# FIT_FPGA_A-C.net
KiCad netlist of a schematic drawn in Altium Designer
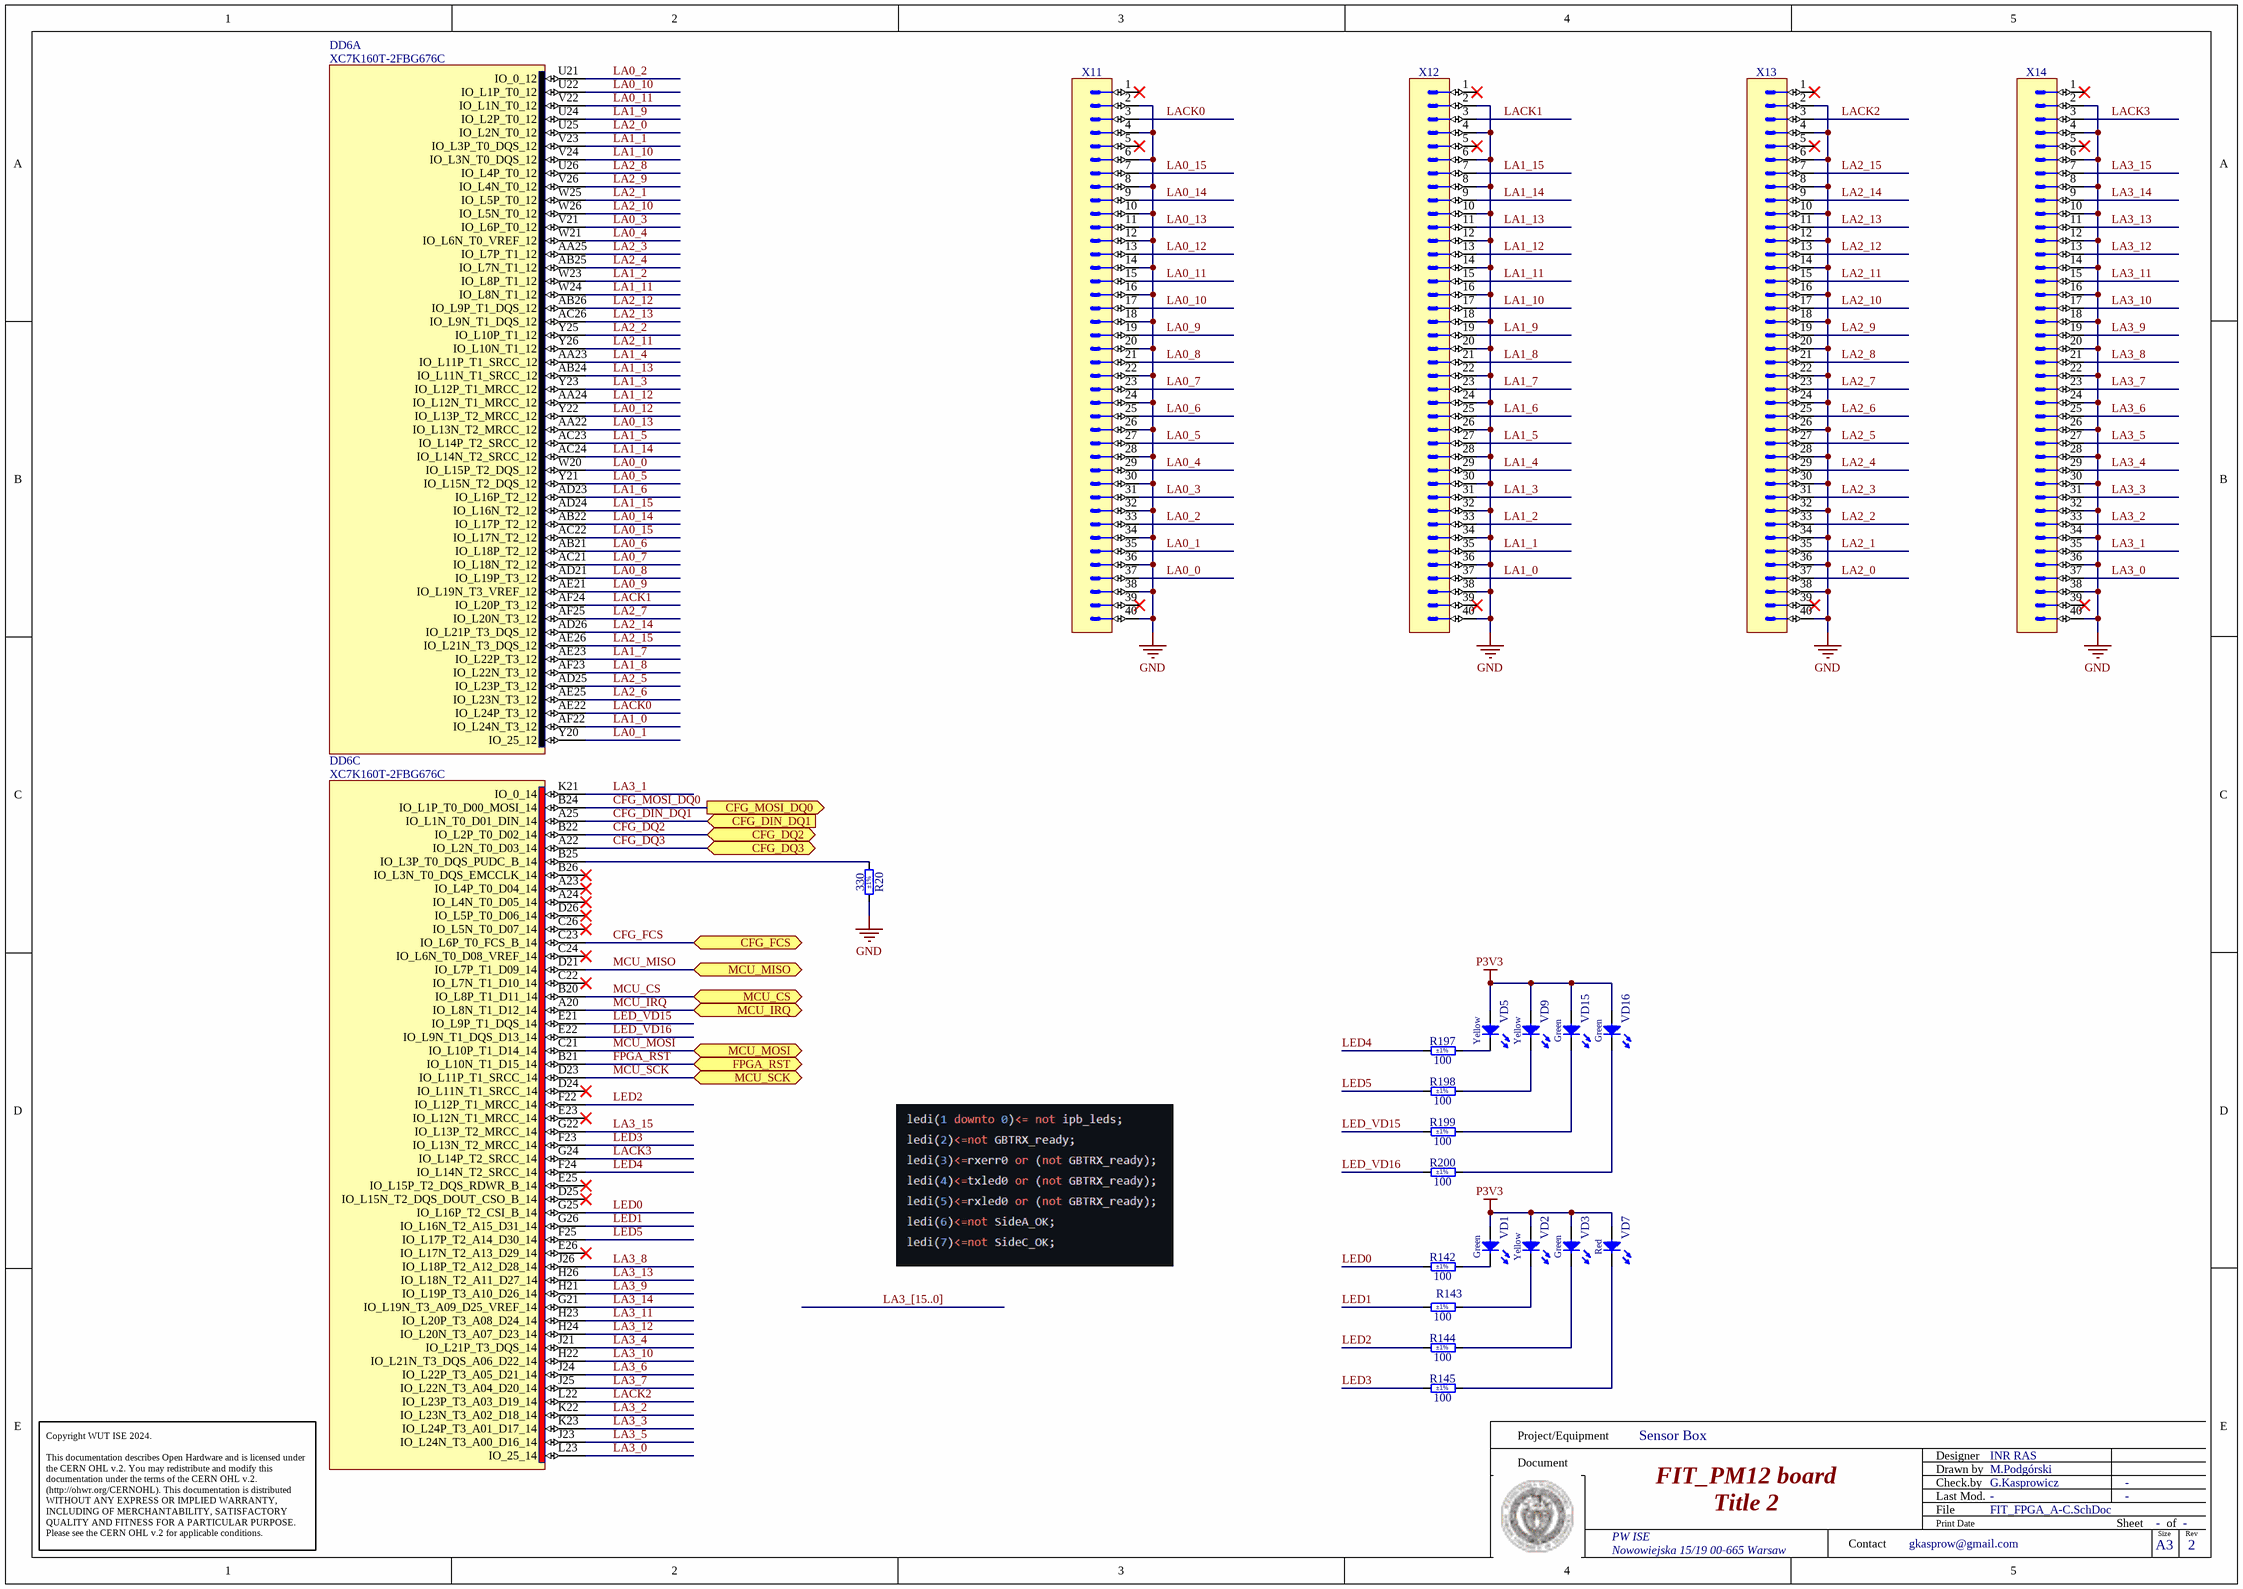
[diagram p0: FIT_FPGA_A-C.SchDoc]

(export (version "E")
  (design (tool "Eeschema 10.0.6"))
  (components
    (comp (ref "DD6")
      (value "XC7K160T-2FBG676C")
      (footprint "BGA676C100P26X26_2700X2700X254")
      (description "KINTEX-7, FPGA, 676-Ball BGA, Pb-Free")
      (fields (field (name "MANUFACTURER") "XILINX") (field (name "AUTHOR") "CERN DEM BC"))
      (libsource (lib "ICs And Semiconductors") (part "XC7K160T-xFBG676"))
    )
    (comp (ref "R20")
      (value "330")
      (footprint "RESC2012X60N")
      (description "Resistor - 1%")
      (fields
        (field (name "TOLERANCE") "±1%")
        (field (name "PART NUMBER") "R0805_330R_1%_0.125W_100PPM")
        (field (name "POWER") "0.125W")
        (field (name "AUTHOR") "CERN DEM JLC")
      )
      (libsource (lib "Resistors") (part "Resistor - 1%"))
    )
    (comp (ref "R142")
      (value "100")
      (footprint "RESC2012X60N")
      (description "Resistor - 1%")
      (fields
        (field (name "TOLERANCE") "±1%")
        (field (name "PART NUMBER") "R0805_100R_1%_0.125W_100PPM")
        (field (name "POWER") "0.125W")
        (field (name "AUTHOR") "CERN DEM JLC")
      )
      (libsource (lib "Resistors") (part "Resistor - 1%"))
    )
    (comp (ref "R143")
      (value "100")
      (footprint "RESC2012X60N")
      (description "Resistor - 1%")
      (fields
        (field (name "TOLERANCE") "±1%")
        (field (name "PART NUMBER") "R0805_100R_1%_0.125W_100PPM")
        (field (name "POWER") "0.125W")
        (field (name "AUTHOR") "CERN DEM JLC")
      )
      (libsource (lib "Resistors") (part "Resistor - 1%"))
    )
    (comp (ref "R144")
      (value "100")
      (footprint "RESC2012X60N")
      (description "Resistor - 1%")
      (fields
        (field (name "TOLERANCE") "±1%")
        (field (name "PART NUMBER") "R0805_100R_1%_0.125W_100PPM")
        (field (name "POWER") "0.125W")
        (field (name "AUTHOR") "CERN DEM JLC")
      )
      (libsource (lib "Resistors") (part "Resistor - 1%"))
    )
    (comp (ref "R145")
      (value "100")
      (footprint "RESC2012X60N")
      (description "Resistor - 1%")
      (fields
        (field (name "TOLERANCE") "±1%")
        (field (name "PART NUMBER") "R0805_100R_1%_0.125W_100PPM")
        (field (name "POWER") "0.125W")
        (field (name "AUTHOR") "CERN DEM JLC")
      )
      (libsource (lib "Resistors") (part "Resistor - 1%"))
    )
    (comp (ref "R197")
      (value "100")
      (footprint "RESC2012X60N")
      (description "Resistor - 1%")
      (fields
        (field (name "TOLERANCE") "±1%")
        (field (name "PART NUMBER") "R0805_100R_1%_0.125W_100PPM")
        (field (name "POWER") "0.125W")
        (field (name "AUTHOR") "CERN DEM JLC")
      )
      (libsource (lib "Resistors") (part "Resistor - 1%"))
    )
    (comp (ref "R198")
      (value "100")
      (footprint "RESC2012X60N")
      (description "Resistor - 1%")
      (fields
        (field (name "TOLERANCE") "±1%")
        (field (name "PART NUMBER") "R0805_100R_1%_0.125W_100PPM")
        (field (name "POWER") "0.125W")
        (field (name "AUTHOR") "CERN DEM JLC")
      )
      (libsource (lib "Resistors") (part "Resistor - 1%"))
    )
    (comp (ref "R199")
      (value "100")
      (footprint "RESC2012X60N")
      (description "Resistor - 1%")
      (fields
        (field (name "TOLERANCE") "±1%")
        (field (name "PART NUMBER") "R0805_100R_1%_0.125W_100PPM")
        (field (name "POWER") "0.125W")
        (field (name "AUTHOR") "CERN DEM JLC")
      )
      (libsource (lib "Resistors") (part "Resistor - 1%"))
    )
    (comp (ref "R200")
      (value "100")
      (footprint "RESC2012X60N")
      (description "Resistor - 1%")
      (fields
        (field (name "TOLERANCE") "±1%")
        (field (name "PART NUMBER") "R0805_100R_1%_0.125W_100PPM")
        (field (name "POWER") "0.125W")
        (field (name "AUTHOR") "CERN DEM JLC")
      )
      (libsource (lib "Resistors") (part "Resistor - 1%"))
    )
    (comp (ref "VD1")
      (value "Green")
      (footprint "LED_KINGBRIGHT_KP-2012LSGC")
      (description "LED Green 1C 2A")
      (fields
        (field (name "PART NUMBER") "LED_KINGBRIGHT_KP-2012LSGC")
        (field (name "MANUFACTURER") "KINGBRIGHT")
        (field (name "AUTHOR") "CERN DEM BC")
      )
      (libsource (lib "ICs And Semiconductors") (part "LED Green 1C 2A"))
    )
    (comp (ref "VD2")
      (value "Yellow")
      (footprint "LED_KINGBRIGHT_KPT-2012YC")
      (description "LED Yellow 1C 2A")
      (fields
        (field (name "PART NUMBER") "LED_KINGBRIGHT_KPT-2012YC")
        (field (name "MANUFACTURER") "KINGBRIGHT")
        (field (name "AUTHOR") "CERN DEM JMW")
      )
      (libsource (lib "ICs And Semiconductors") (part "LED Yellow 1C 2A"))
    )
    (comp (ref "VD3")
      (value "Green")
      (footprint "LED_KINGBRIGHT_KP-2012LSGC")
      (description "LED Green 1C 2A")
      (fields
        (field (name "PART NUMBER") "LED_KINGBRIGHT_KP-2012LSGC")
        (field (name "MANUFACTURER") "KINGBRIGHT")
        (field (name "AUTHOR") "CERN DEM BC")
      )
      (libsource (lib "ICs And Semiconductors") (part "LED Green 1C 2A"))
    )
    (comp (ref "VD5")
      (value "Yellow")
      (footprint "LED_KINGBRIGHT_KPT-2012YC")
      (description "LED Yellow 1C 2A")
      (fields
        (field (name "PART NUMBER") "LED_KINGBRIGHT_KPT-2012YC")
        (field (name "MANUFACTURER") "KINGBRIGHT")
        (field (name "AUTHOR") "CERN DEM JMW")
      )
      (libsource (lib "ICs And Semiconductors") (part "LED Yellow 1C 2A"))
    )
    (comp (ref "VD7")
      (value "Red")
      (footprint "LED_KINGBRIGHT_KPT-2012SURCK")
      (description "LED Red 1C 2A")
      (fields
        (field (name "PART NUMBER") "LED_KINGBRIGHT_KPT-2012SURCK")
        (field (name "MANUFACTURER") "KINGBRIGHT")
        (field (name "AUTHOR") "CERN DEM BC")
      )
      (libsource (lib "ICs And Semiconductors") (part "LED Red 1C 2A"))
    )
    (comp (ref "VD9")
      (value "Yellow")
      (footprint "LED_KINGBRIGHT_KPT-2012YC")
      (description "LED Yellow 1C 2A")
      (fields
        (field (name "PART NUMBER") "LED_KINGBRIGHT_KPT-2012YC")
        (field (name "MANUFACTURER") "KINGBRIGHT")
        (field (name "AUTHOR") "CERN DEM JMW")
      )
      (libsource (lib "ICs And Semiconductors") (part "LED Yellow 1C 2A"))
    )
    (comp (ref "VD15")
      (value "Green")
      (footprint "LED_KINGBRIGHT_KP-2012LSGC")
      (description "LED Green 1C 2A")
      (fields
        (field (name "PART NUMBER") "LED_KINGBRIGHT_KP-2012LSGC")
        (field (name "MANUFACTURER") "KINGBRIGHT")
        (field (name "AUTHOR") "CERN DEM BC")
      )
      (libsource (lib "ICs And Semiconductors") (part "LED Green 1C 2A"))
    )
    (comp (ref "VD16")
      (value "Green")
      (footprint "LED_KINGBRIGHT_KP-2012LSGC")
      (description "LED Green 1C 2A")
      (fields
        (field (name "PART NUMBER") "LED_KINGBRIGHT_KP-2012LSGC")
        (field (name "MANUFACTURER") "KINGBRIGHT")
        (field (name "AUTHOR") "CERN DEM BC")
      )
      (libsource (lib "ICs And Semiconductors") (part "LED Green 1C 2A"))
    )
    (comp (ref "X11")
      (value "~")
      (footprint "CONNFLY_DS1013-40SSIB1-B-0")
      (description "Connector 40 Male")
      (fields
        (field (name "PART NUMBER") "CONNFLY_DS1013-40SSIB1-B-0")
        (field (name "MANUFACTURER") "CONNFLY")
        (field (name "AUTHOR") "CERN DEM HF")
      )
      (libsource (lib "Connectors") (part "Connector 40 Male"))
    )
    (comp (ref "X12")
      (value "~")
      (footprint "CONNFLY_DS1013-40SSIB1-B-0")
      (description "Connector 40 Male")
      (fields
        (field (name "PART NUMBER") "CONNFLY_DS1013-40SSIB1-B-0")
        (field (name "MANUFACTURER") "CONNFLY")
        (field (name "AUTHOR") "CERN DEM HF")
      )
      (libsource (lib "Connectors") (part "Connector 40 Male"))
    )
    (comp (ref "X13")
      (value "~")
      (footprint "CONNFLY_DS1013-40SSIB1-B-0")
      (description "Connector 40 Male")
      (fields
        (field (name "PART NUMBER") "CONNFLY_DS1013-40SSIB1-B-0")
        (field (name "MANUFACTURER") "CONNFLY")
        (field (name "AUTHOR") "CERN DEM HF")
      )
      (libsource (lib "Connectors") (part "Connector 40 Male"))
    )
    (comp (ref "X14")
      (value "~")
      (footprint "CONNFLY_DS1013-40SSIB1-B-0")
      (description "Connector 40 Male")
      (fields
        (field (name "PART NUMBER") "CONNFLY_DS1013-40SSIB1-B-0")
        (field (name "MANUFACTURER") "CONNFLY")
        (field (name "AUTHOR") "CERN DEM HF")
      )
      (libsource (lib "Connectors") (part "Connector 40 Male"))
    )
  )
  (nets
    (net (code "1") (name "/CFG_DIN_DQ1") (class "Default")
      (node (ref "DD6") (pin "A25") (pinfunction "IO_L1N_T0_D01_DIN_14_A25") (pintype "bidirectional"))
    )
    (net (code "2") (name "/CFG_DQ2") (class "Default")
      (node (ref "DD6") (pin "B22") (pinfunction "IO_L2P_T0_D02_14_B22") (pintype "bidirectional"))
    )
    (net (code "3") (name "/CFG_DQ3") (class "Default")
      (node (ref "DD6") (pin "A22") (pinfunction "IO_L2N_T0_D03_14_A22") (pintype "bidirectional"))
    )
    (net (code "4") (name "/CFG_FCS") (class "Default")
      (node (ref "DD6") (pin "C23") (pinfunction "IO_L6P_T0_FCS_B_14_C23") (pintype "bidirectional"))
    )
    (net (code "5") (name "/CFG_MOSI_DQ0") (class "Default")
      (node (ref "DD6") (pin "B24") (pinfunction "IO_L1P_T0_D00_MOSI_14_B24") (pintype "bidirectional"))
    )
    (net (code "6") (name "/FPGA_RST") (class "Default")
      (node (ref "DD6") (pin "B21") (pinfunction "IO_L10N_T1_D15_14_B21") (pintype "bidirectional"))
    )
    (net (code "7") (name "/LA0_0") (class "Default")
      (node (ref "DD6") (pin "W20") (pinfunction "IO_L15P_T2_DQS_12_W20") (pintype "bidirectional"))
      (node (ref "X11") (pin "37") (pinfunction "37_37") (pintype "bidirectional"))
    )
    (net (code "8") (name "/LA0_1") (class "Default")
      (node (ref "DD6") (pin "Y20") (pinfunction "IO_25_12_Y20") (pintype "bidirectional"))
      (node (ref "X11") (pin "35") (pinfunction "35_35") (pintype "bidirectional"))
    )
    (net (code "9") (name "/LA0_2") (class "Default")
      (node (ref "DD6") (pin "U21") (pinfunction "IO_0_12_U21") (pintype "bidirectional"))
      (node (ref "X11") (pin "33") (pinfunction "33_33") (pintype "bidirectional"))
    )
    (net (code "10") (name "/LA0_3") (class "Default")
      (node (ref "DD6") (pin "V21") (pinfunction "IO_L6P_T0_12_V21") (pintype "bidirectional"))
      (node (ref "X11") (pin "31") (pinfunction "31_31") (pintype "bidirectional"))
    )
    (net (code "11") (name "/LA0_4") (class "Default")
      (node (ref "DD6") (pin "W21") (pinfunction "IO_L6N_T0_VREF_12_W21") (pintype "bidirectional"))
      (node (ref "X11") (pin "29") (pinfunction "29_29") (pintype "bidirectional"))
    )
    (net (code "12") (name "/LA0_5") (class "Default")
      (node (ref "DD6") (pin "Y21") (pinfunction "IO_L15N_T2_DQS_12_Y21") (pintype "bidirectional"))
      (node (ref "X11") (pin "27") (pinfunction "27_27") (pintype "bidirectional"))
    )
    (net (code "13") (name "/LA0_6") (class "Default")
      (node (ref "DD6") (pin "AB21") (pinfunction "IO_L18P_T2_12_AB21") (pintype "bidirectional"))
      (node (ref "X11") (pin "25") (pinfunction "25_25") (pintype "bidirectional"))
    )
    (net (code "14") (name "/LA0_7") (class "Default")
      (node (ref "DD6") (pin "AC21") (pinfunction "IO_L18N_T2_12_AC21") (pintype "bidirectional"))
      (node (ref "X11") (pin "23") (pinfunction "23_23") (pintype "bidirectional"))
    )
    (net (code "15") (name "/LA0_8") (class "Default")
      (node (ref "DD6") (pin "AD21") (pinfunction "IO_L19P_T3_12_AD21") (pintype "bidirectional"))
      (node (ref "X11") (pin "21") (pinfunction "21_21") (pintype "bidirectional"))
    )
    (net (code "16") (name "/LA0_9") (class "Default")
      (node (ref "DD6") (pin "AE21") (pinfunction "IO_L19N_T3_VREF_12_AE21") (pintype "bidirectional"))
      (node (ref "X11") (pin "19") (pinfunction "19_19") (pintype "bidirectional"))
    )
    (net (code "17") (name "/LA0_10") (class "Default")
      (node (ref "DD6") (pin "U22") (pinfunction "IO_L1P_T0_12_U22") (pintype "bidirectional"))
      (node (ref "X11") (pin "17") (pinfunction "17_17") (pintype "bidirectional"))
    )
    (net (code "18") (name "/LA0_11") (class "Default")
      (node (ref "DD6") (pin "V22") (pinfunction "IO_L1N_T0_12_V22") (pintype "bidirectional"))
      (node (ref "X11") (pin "15") (pinfunction "15_15") (pintype "bidirectional"))
    )
    (net (code "19") (name "/LA0_12") (class "Default")
      (node (ref "DD6") (pin "Y22") (pinfunction "IO_L13P_T2_MRCC_12_Y22") (pintype "bidirectional"))
      (node (ref "X11") (pin "13") (pinfunction "13_13") (pintype "bidirectional"))
    )
    (net (code "20") (name "/LA0_13") (class "Default")
      (node (ref "DD6") (pin "AA22") (pinfunction "IO_L13N_T2_MRCC_12_AA22") (pintype "bidirectional"))
      (node (ref "X11") (pin "11") (pinfunction "11_11") (pintype "bidirectional"))
    )
    (net (code "21") (name "/LA0_14") (class "Default")
      (node (ref "DD6") (pin "AB22") (pinfunction "IO_L17P_T2_12_AB22") (pintype "bidirectional"))
      (node (ref "X11") (pin "9") (pinfunction "9_9") (pintype "bidirectional"))
    )
    (net (code "22") (name "/LA0_15") (class "Default")
      (node (ref "DD6") (pin "AC22") (pinfunction "IO_L17N_T2_12_AC22") (pintype "bidirectional"))
      (node (ref "X11") (pin "7") (pinfunction "7_7") (pintype "bidirectional"))
    )
    (net (code "23") (name "/LA1_0") (class "Default")
      (node (ref "DD6") (pin "AF22") (pinfunction "IO_L24N_T3_12_AF22") (pintype "bidirectional"))
      (node (ref "X12") (pin "37") (pinfunction "37_37") (pintype "bidirectional"))
    )
    (net (code "24") (name "/LA1_1") (class "Default")
      (node (ref "DD6") (pin "V23") (pinfunction "IO_L3P_T0_DQS_12_V23") (pintype "bidirectional"))
      (node (ref "X12") (pin "35") (pinfunction "35_35") (pintype "bidirectional"))
    )
    (net (code "25") (name "/LA1_2") (class "Default")
      (node (ref "DD6") (pin "W23") (pinfunction "IO_L8P_T1_12_W23") (pintype "bidirectional"))
      (node (ref "X12") (pin "33") (pinfunction "33_33") (pintype "bidirectional"))
    )
    (net (code "26") (name "/LA1_3") (class "Default")
      (node (ref "DD6") (pin "Y23") (pinfunction "IO_L12P_T1_MRCC_12_Y23") (pintype "bidirectional"))
      (node (ref "X12") (pin "31") (pinfunction "31_31") (pintype "bidirectional"))
    )
    (net (code "27") (name "/LA1_4") (class "Default")
      (node (ref "DD6") (pin "AA23") (pinfunction "IO_L11P_T1_SRCC_12_AA23") (pintype "bidirectional"))
      (node (ref "X12") (pin "29") (pinfunction "29_29") (pintype "bidirectional"))
    )
    (net (code "28") (name "/LA1_5") (class "Default")
      (node (ref "DD6") (pin "AC23") (pinfunction "IO_L14P_T2_SRCC_12_AC23") (pintype "bidirectional"))
      (node (ref "X12") (pin "27") (pinfunction "27_27") (pintype "bidirectional"))
    )
    (net (code "29") (name "/LA1_6") (class "Default")
      (node (ref "DD6") (pin "AD23") (pinfunction "IO_L16P_T2_12_AD23") (pintype "bidirectional"))
      (node (ref "X12") (pin "25") (pinfunction "25_25") (pintype "bidirectional"))
    )
    (net (code "30") (name "/LA1_7") (class "Default")
      (node (ref "DD6") (pin "AE23") (pinfunction "IO_L22P_T3_12_AE23") (pintype "bidirectional"))
      (node (ref "X12") (pin "23") (pinfunction "23_23") (pintype "bidirectional"))
    )
    (net (code "31") (name "/LA1_8") (class "Default")
      (node (ref "DD6") (pin "AF23") (pinfunction "IO_L22N_T3_12_AF23") (pintype "bidirectional"))
      (node (ref "X12") (pin "21") (pinfunction "21_21") (pintype "bidirectional"))
    )
    (net (code "32") (name "/LA1_9") (class "Default")
      (node (ref "DD6") (pin "U24") (pinfunction "IO_L2P_T0_12_U24") (pintype "bidirectional"))
      (node (ref "X12") (pin "19") (pinfunction "19_19") (pintype "bidirectional"))
    )
    (net (code "33") (name "/LA1_10") (class "Default")
      (node (ref "DD6") (pin "V24") (pinfunction "IO_L3N_T0_DQS_12_V24") (pintype "bidirectional"))
      (node (ref "X12") (pin "17") (pinfunction "17_17") (pintype "bidirectional"))
    )
    (net (code "34") (name "/LA1_11") (class "Default")
      (node (ref "DD6") (pin "W24") (pinfunction "IO_L8N_T1_12_W24") (pintype "bidirectional"))
      (node (ref "X12") (pin "15") (pinfunction "15_15") (pintype "bidirectional"))
    )
    (net (code "35") (name "/LA1_12") (class "Default")
      (node (ref "DD6") (pin "AA24") (pinfunction "IO_L12N_T1_MRCC_12_AA24") (pintype "bidirectional"))
      (node (ref "X12") (pin "13") (pinfunction "13_13") (pintype "bidirectional"))
    )
    (net (code "36") (name "/LA1_13") (class "Default")
      (node (ref "DD6") (pin "AB24") (pinfunction "IO_L11N_T1_SRCC_12_AB24") (pintype "bidirectional"))
      (node (ref "X12") (pin "11") (pinfunction "11_11") (pintype "bidirectional"))
    )
    (net (code "37") (name "/LA1_14") (class "Default")
      (node (ref "DD6") (pin "AC24") (pinfunction "IO_L14N_T2_SRCC_12_AC24") (pintype "bidirectional"))
      (node (ref "X12") (pin "9") (pinfunction "9_9") (pintype "bidirectional"))
    )
    (net (code "38") (name "/LA1_15") (class "Default")
      (node (ref "DD6") (pin "AD24") (pinfunction "IO_L16N_T2_12_AD24") (pintype "bidirectional"))
      (node (ref "X12") (pin "7") (pinfunction "7_7") (pintype "bidirectional"))
    )
    (net (code "39") (name "/LA2_0") (class "Default")
      (node (ref "DD6") (pin "U25") (pinfunction "IO_L2N_T0_12_U25") (pintype "bidirectional"))
      (node (ref "X13") (pin "37") (pinfunction "37_37") (pintype "bidirectional"))
    )
    (net (code "40") (name "/LA2_1") (class "Default")
      (node (ref "DD6") (pin "W25") (pinfunction "IO_L5P_T0_12_W25") (pintype "bidirectional"))
      (node (ref "X13") (pin "35") (pinfunction "35_35") (pintype "bidirectional"))
    )
    (net (code "41") (name "/LA2_2") (class "Default")
      (node (ref "DD6") (pin "Y25") (pinfunction "IO_L10P_T1_12_Y25") (pintype "bidirectional"))
      (node (ref "X13") (pin "33") (pinfunction "33_33") (pintype "bidirectional"))
    )
    (net (code "42") (name "/LA2_3") (class "Default")
      (node (ref "DD6") (pin "AA25") (pinfunction "IO_L7P_T1_12_AA25") (pintype "bidirectional"))
      (node (ref "X13") (pin "31") (pinfunction "31_31") (pintype "bidirectional"))
    )
    (net (code "43") (name "/LA2_4") (class "Default")
      (node (ref "DD6") (pin "AB25") (pinfunction "IO_L7N_T1_12_AB25") (pintype "bidirectional"))
      (node (ref "X13") (pin "29") (pinfunction "29_29") (pintype "bidirectional"))
    )
    (net (code "44") (name "/LA2_5") (class "Default")
      (node (ref "DD6") (pin "AD25") (pinfunction "IO_L23P_T3_12_AD25") (pintype "bidirectional"))
      (node (ref "X13") (pin "27") (pinfunction "27_27") (pintype "bidirectional"))
    )
    (net (code "45") (name "/LA2_6") (class "Default")
      (node (ref "DD6") (pin "AE25") (pinfunction "IO_L23N_T3_12_AE25") (pintype "bidirectional"))
      (node (ref "X13") (pin "25") (pinfunction "25_25") (pintype "bidirectional"))
    )
    (net (code "46") (name "/LA2_7") (class "Default")
      (node (ref "DD6") (pin "AF25") (pinfunction "IO_L20N_T3_12_AF25") (pintype "bidirectional"))
      (node (ref "X13") (pin "23") (pinfunction "23_23") (pintype "bidirectional"))
    )
    (net (code "47") (name "/LA2_8") (class "Default")
      (node (ref "DD6") (pin "U26") (pinfunction "IO_L4P_T0_12_U26") (pintype "bidirectional"))
      (node (ref "X13") (pin "21") (pinfunction "21_21") (pintype "bidirectional"))
    )
    (net (code "48") (name "/LA2_9") (class "Default")
      (node (ref "DD6") (pin "V26") (pinfunction "IO_L4N_T0_12_V26") (pintype "bidirectional"))
      (node (ref "X13") (pin "19") (pinfunction "19_19") (pintype "bidirectional"))
    )
    (net (code "49") (name "/LA2_10") (class "Default")
      (node (ref "DD6") (pin "W26") (pinfunction "IO_L5N_T0_12_W26") (pintype "bidirectional"))
      (node (ref "X13") (pin "17") (pinfunction "17_17") (pintype "bidirectional"))
    )
    (net (code "50") (name "/LA2_11") (class "Default")
      (node (ref "DD6") (pin "Y26") (pinfunction "IO_L10N_T1_12_Y26") (pintype "bidirectional"))
      (node (ref "X13") (pin "15") (pinfunction "15_15") (pintype "bidirectional"))
    )
    (net (code "51") (name "/LA2_12") (class "Default")
      (node (ref "DD6") (pin "AB26") (pinfunction "IO_L9P_T1_DQS_12_AB26") (pintype "bidirectional"))
      (node (ref "X13") (pin "13") (pinfunction "13_13") (pintype "bidirectional"))
    )
    (net (code "52") (name "/LA2_13") (class "Default")
      (node (ref "DD6") (pin "AC26") (pinfunction "IO_L9N_T1_DQS_12_AC26") (pintype "bidirectional"))
      (node (ref "X13") (pin "11") (pinfunction "11_11") (pintype "bidirectional"))
    )
    (net (code "53") (name "/LA2_14") (class "Default")
      (node (ref "DD6") (pin "AD26") (pinfunction "IO_L21P_T3_DQS_12_AD26") (pintype "bidirectional"))
      (node (ref "X13") (pin "9") (pinfunction "9_9") (pintype "bidirectional"))
    )
    (net (code "54") (name "/LA2_15") (class "Default")
      (node (ref "DD6") (pin "AE26") (pinfunction "IO_L21N_T3_DQS_12_AE26") (pintype "bidirectional"))
      (node (ref "X13") (pin "7") (pinfunction "7_7") (pintype "bidirectional"))
    )
    (net (code "55") (name "/LA3_0") (class "Default")
      (node (ref "DD6") (pin "L23") (pinfunction "IO_25_14_L23") (pintype "bidirectional"))
      (node (ref "X14") (pin "37") (pinfunction "37_37") (pintype "bidirectional"))
    )
    (net (code "56") (name "/LA3_1") (class "Default")
      (node (ref "DD6") (pin "K21") (pinfunction "IO_0_14_K21") (pintype "bidirectional"))
      (node (ref "X14") (pin "35") (pinfunction "35_35") (pintype "bidirectional"))
    )
    (net (code "57") (name "/LA3_2") (class "Default")
      (node (ref "DD6") (pin "K22") (pinfunction "IO_L23N_T3_A02_D18_14_K22") (pintype "bidirectional"))
      (node (ref "X14") (pin "33") (pinfunction "33_33") (pintype "bidirectional"))
    )
    (net (code "58") (name "/LA3_3") (class "Default")
      (node (ref "DD6") (pin "K23") (pinfunction "IO_L24P_T3_A01_D17_14_K23") (pintype "bidirectional"))
      (node (ref "X14") (pin "31") (pinfunction "31_31") (pintype "bidirectional"))
    )
    (net (code "59") (name "/LA3_4") (class "Default")
      (node (ref "DD6") (pin "J21") (pinfunction "IO_L21P_T3_DQS_14_J21") (pintype "bidirectional"))
      (node (ref "X14") (pin "29") (pinfunction "29_29") (pintype "bidirectional"))
    )
    (net (code "60") (name "/LA3_5") (class "Default")
      (node (ref "DD6") (pin "J23") (pinfunction "IO_L24N_T3_A00_D16_14_J23") (pintype "bidirectional"))
      (node (ref "X14") (pin "27") (pinfunction "27_27") (pintype "bidirectional"))
    )
    (net (code "61") (name "/LA3_6") (class "Default")
      (node (ref "DD6") (pin "J24") (pinfunction "IO_L22P_T3_A05_D21_14_J24") (pintype "bidirectional"))
      (node (ref "X14") (pin "25") (pinfunction "25_25") (pintype "bidirectional"))
    )
    (net (code "62") (name "/LA3_7") (class "Default")
      (node (ref "DD6") (pin "J25") (pinfunction "IO_L22N_T3_A04_D20_14_J25") (pintype "bidirectional"))
      (node (ref "X14") (pin "23") (pinfunction "23_23") (pintype "bidirectional"))
    )
    (net (code "63") (name "/LA3_8") (class "Default")
      (node (ref "DD6") (pin "J26") (pinfunction "IO_L18P_T2_A12_D28_14_J26") (pintype "bidirectional"))
      (node (ref "X14") (pin "21") (pinfunction "21_21") (pintype "bidirectional"))
    )
    (net (code "64") (name "/LA3_9") (class "Default")
      (node (ref "DD6") (pin "H21") (pinfunction "IO_L19P_T3_A10_D26_14_H21") (pintype "bidirectional"))
      (node (ref "X14") (pin "19") (pinfunction "19_19") (pintype "bidirectional"))
    )
    (net (code "65") (name "/LA3_10") (class "Default")
      (node (ref "DD6") (pin "H22") (pinfunction "IO_L21N_T3_DQS_A06_D22_14_H22") (pintype "bidirectional"))
      (node (ref "X14") (pin "17") (pinfunction "17_17") (pintype "bidirectional"))
    )
    (net (code "66") (name "/LA3_11") (class "Default")
      (node (ref "DD6") (pin "H23") (pinfunction "IO_L20P_T3_A08_D24_14_H23") (pintype "bidirectional"))
      (node (ref "X14") (pin "15") (pinfunction "15_15") (pintype "bidirectional"))
    )
    (net (code "67") (name "/LA3_12") (class "Default")
      (node (ref "DD6") (pin "H24") (pinfunction "IO_L20N_T3_A07_D23_14_H24") (pintype "bidirectional"))
      (node (ref "X14") (pin "13") (pinfunction "13_13") (pintype "bidirectional"))
    )
    (net (code "68") (name "/LA3_13") (class "Default")
      (node (ref "DD6") (pin "H26") (pinfunction "IO_L18N_T2_A11_D27_14_H26") (pintype "bidirectional"))
      (node (ref "X14") (pin "11") (pinfunction "11_11") (pintype "bidirectional"))
    )
    (net (code "69") (name "/LA3_14") (class "Default")
      (node (ref "DD6") (pin "G21") (pinfunction "IO_L19N_T3_A09_D25_VREF_14_G21") (pintype "bidirectional"))
      (node (ref "X14") (pin "9") (pinfunction "9_9") (pintype "bidirectional"))
    )
    (net (code "70") (name "/LA3_15") (class "Default")
      (node (ref "DD6") (pin "G22") (pinfunction "IO_L13P_T2_MRCC_14_G22") (pintype "bidirectional"))
      (node (ref "X14") (pin "7") (pinfunction "7_7") (pintype "bidirectional"))
    )
    (net (code "72") (name "/LACK0") (class "Default")
      (node (ref "DD6") (pin "AE22") (pinfunction "IO_L24P_T3_12_AE22") (pintype "bidirectional"))
      (node (ref "X11") (pin "3") (pinfunction "3_3") (pintype "bidirectional"))
    )
    (net (code "73") (name "/LACK1") (class "Default")
      (node (ref "DD6") (pin "AF24") (pinfunction "IO_L20P_T3_12_AF24") (pintype "bidirectional"))
      (node (ref "X12") (pin "3") (pinfunction "3_3") (pintype "bidirectional"))
    )
    (net (code "74") (name "/LACK2") (class "Default")
      (node (ref "DD6") (pin "L22") (pinfunction "IO_L23P_T3_A03_D19_14_L22") (pintype "bidirectional"))
      (node (ref "X13") (pin "3") (pinfunction "3_3") (pintype "bidirectional"))
    )
    (net (code "75") (name "/LACK3") (class "Default")
      (node (ref "DD6") (pin "G24") (pinfunction "IO_L14P_T2_SRCC_14_G24") (pintype "bidirectional"))
      (node (ref "X14") (pin "3") (pinfunction "3_3") (pintype "bidirectional"))
    )
    (net (code "76") (name "/LED0") (class "Default")
      (node (ref "DD6") (pin "G25") (pinfunction "IO_L16P_T2_CSI_B_14_G25") (pintype "bidirectional"))
      (node (ref "R142") (pin "1") (pinfunction "1_1") (pintype "passive"))
    )
    (net (code "77") (name "/LED1") (class "Default")
      (node (ref "DD6") (pin "G26") (pinfunction "IO_L16N_T2_A15_D31_14_G26") (pintype "bidirectional"))
      (node (ref "R143") (pin "1") (pinfunction "1_1") (pintype "passive"))
    )
    (net (code "78") (name "/LED2") (class "Default")
      (node (ref "DD6") (pin "F22") (pinfunction "IO_L12P_T1_MRCC_14_F22") (pintype "bidirectional"))
      (node (ref "R144") (pin "1") (pinfunction "1_1") (pintype "passive"))
    )
    (net (code "79") (name "/LED3") (class "Default")
      (node (ref "DD6") (pin "F23") (pinfunction "IO_L13N_T2_MRCC_14_F23") (pintype "bidirectional"))
      (node (ref "R145") (pin "1") (pinfunction "1_1") (pintype "passive"))
    )
    (net (code "80") (name "/LED4") (class "Default")
      (node (ref "DD6") (pin "F24") (pinfunction "IO_L14N_T2_SRCC_14_F24") (pintype "bidirectional"))
      (node (ref "R197") (pin "1") (pinfunction "1_1") (pintype "passive"))
    )
    (net (code "81") (name "/LED5") (class "Default")
      (node (ref "DD6") (pin "F25") (pinfunction "IO_L17P_T2_A14_D30_14_F25") (pintype "bidirectional"))
      (node (ref "R198") (pin "1") (pinfunction "1_1") (pintype "passive"))
    )
    (net (code "82") (name "/LED_VD15") (class "Default")
      (node (ref "DD6") (pin "E21") (pinfunction "IO_L9P_T1_DQS_14_E21") (pintype "bidirectional"))
      (node (ref "R199") (pin "1") (pinfunction "1_1") (pintype "passive"))
    )
    (net (code "83") (name "/LED_VD16") (class "Default")
      (node (ref "DD6") (pin "E22") (pinfunction "IO_L9N_T1_DQS_D13_14_E22") (pintype "bidirectional"))
      (node (ref "R200") (pin "1") (pinfunction "1_1") (pintype "passive"))
    )
    (net (code "84") (name "/MCU_CS") (class "Default")
      (node (ref "DD6") (pin "B20") (pinfunction "IO_L8P_T1_D11_14_B20") (pintype "bidirectional"))
    )
    (net (code "85") (name "/MCU_IRQ") (class "Default")
      (node (ref "DD6") (pin "A20") (pinfunction "IO_L8N_T1_D12_14_A20") (pintype "bidirectional"))
    )
    (net (code "86") (name "/MCU_MISO") (class "Default")
      (node (ref "DD6") (pin "D21") (pinfunction "IO_L7P_T1_D09_14_D21") (pintype "bidirectional"))
    )
    (net (code "87") (name "/MCU_MOSI") (class "Default")
      (node (ref "DD6") (pin "C21") (pinfunction "IO_L10P_T1_D14_14_C21") (pintype "bidirectional"))
    )
    (net (code "88") (name "/MCU_SCK") (class "Default")
      (node (ref "DD6") (pin "D23") (pinfunction "IO_L11P_T1_SRCC_14_D23") (pintype "bidirectional"))
    )
    (net (code "89") (name "GND") (class "Default")
      (node (ref "R20") (pin "2") (pinfunction "2_2") (pintype "passive"))
      (node (ref "X11") (pin "10") (pinfunction "10_10") (pintype "bidirectional"))
      (node (ref "X11") (pin "12") (pinfunction "12_12") (pintype "bidirectional"))
      (node (ref "X11") (pin "14") (pinfunction "14_14") (pintype "bidirectional"))
      (node (ref "X11") (pin "16") (pinfunction "16_16") (pintype "bidirectional"))
      (node (ref "X11") (pin "18") (pinfunction "18_18") (pintype "bidirectional"))
      (node (ref "X11") (pin "2") (pinfunction "2_2") (pintype "bidirectional"))
      (node (ref "X11") (pin "20") (pinfunction "20_20") (pintype "bidirectional"))
      (node (ref "X11") (pin "22") (pinfunction "22_22") (pintype "bidirectional"))
      (node (ref "X11") (pin "24") (pinfunction "24_24") (pintype "bidirectional"))
      (node (ref "X11") (pin "26") (pinfunction "26_26") (pintype "bidirectional"))
      (node (ref "X11") (pin "28") (pinfunction "28_28") (pintype "bidirectional"))
      (node (ref "X11") (pin "30") (pinfunction "30_30") (pintype "bidirectional"))
      (node (ref "X11") (pin "32") (pinfunction "32_32") (pintype "bidirectional"))
      (node (ref "X11") (pin "34") (pinfunction "34_34") (pintype "bidirectional"))
      (node (ref "X11") (pin "36") (pinfunction "36_36") (pintype "bidirectional"))
      (node (ref "X11") (pin "38") (pinfunction "38_38") (pintype "bidirectional"))
      (node (ref "X11") (pin "4") (pinfunction "4_4") (pintype "bidirectional"))
      (node (ref "X11") (pin "40") (pinfunction "40_40") (pintype "bidirectional"))
      (node (ref "X11") (pin "6") (pinfunction "6_6") (pintype "bidirectional"))
      (node (ref "X11") (pin "8") (pinfunction "8_8") (pintype "bidirectional"))
      (node (ref "X12") (pin "10") (pinfunction "10_10") (pintype "bidirectional"))
      (node (ref "X12") (pin "12") (pinfunction "12_12") (pintype "bidirectional"))
      (node (ref "X12") (pin "14") (pinfunction "14_14") (pintype "bidirectional"))
      (node (ref "X12") (pin "16") (pinfunction "16_16") (pintype "bidirectional"))
      (node (ref "X12") (pin "18") (pinfunction "18_18") (pintype "bidirectional"))
      (node (ref "X12") (pin "2") (pinfunction "2_2") (pintype "bidirectional"))
      (node (ref "X12") (pin "20") (pinfunction "20_20") (pintype "bidirectional"))
      (node (ref "X12") (pin "22") (pinfunction "22_22") (pintype "bidirectional"))
      (node (ref "X12") (pin "24") (pinfunction "24_24") (pintype "bidirectional"))
      (node (ref "X12") (pin "26") (pinfunction "26_26") (pintype "bidirectional"))
      (node (ref "X12") (pin "28") (pinfunction "28_28") (pintype "bidirectional"))
      (node (ref "X12") (pin "30") (pinfunction "30_30") (pintype "bidirectional"))
      (node (ref "X12") (pin "32") (pinfunction "32_32") (pintype "bidirectional"))
      (node (ref "X12") (pin "34") (pinfunction "34_34") (pintype "bidirectional"))
      (node (ref "X12") (pin "36") (pinfunction "36_36") (pintype "bidirectional"))
      (node (ref "X12") (pin "38") (pinfunction "38_38") (pintype "bidirectional"))
      (node (ref "X12") (pin "4") (pinfunction "4_4") (pintype "bidirectional"))
      (node (ref "X12") (pin "40") (pinfunction "40_40") (pintype "bidirectional"))
      (node (ref "X12") (pin "6") (pinfunction "6_6") (pintype "bidirectional"))
      (node (ref "X12") (pin "8") (pinfunction "8_8") (pintype "bidirectional"))
      (node (ref "X13") (pin "10") (pinfunction "10_10") (pintype "bidirectional"))
      (node (ref "X13") (pin "12") (pinfunction "12_12") (pintype "bidirectional"))
      (node (ref "X13") (pin "14") (pinfunction "14_14") (pintype "bidirectional"))
      (node (ref "X13") (pin "16") (pinfunction "16_16") (pintype "bidirectional"))
      (node (ref "X13") (pin "18") (pinfunction "18_18") (pintype "bidirectional"))
      (node (ref "X13") (pin "2") (pinfunction "2_2") (pintype "bidirectional"))
      (node (ref "X13") (pin "20") (pinfunction "20_20") (pintype "bidirectional"))
      (node (ref "X13") (pin "22") (pinfunction "22_22") (pintype "bidirectional"))
      (node (ref "X13") (pin "24") (pinfunction "24_24") (pintype "bidirectional"))
      (node (ref "X13") (pin "26") (pinfunction "26_26") (pintype "bidirectional"))
      (node (ref "X13") (pin "28") (pinfunction "28_28") (pintype "bidirectional"))
      (node (ref "X13") (pin "30") (pinfunction "30_30") (pintype "bidirectional"))
      (node (ref "X13") (pin "32") (pinfunction "32_32") (pintype "bidirectional"))
      (node (ref "X13") (pin "34") (pinfunction "34_34") (pintype "bidirectional"))
      (node (ref "X13") (pin "36") (pinfunction "36_36") (pintype "bidirectional"))
      (node (ref "X13") (pin "38") (pinfunction "38_38") (pintype "bidirectional"))
      (node (ref "X13") (pin "4") (pinfunction "4_4") (pintype "bidirectional"))
      (node (ref "X13") (pin "40") (pinfunction "40_40") (pintype "bidirectional"))
      (node (ref "X13") (pin "6") (pinfunction "6_6") (pintype "bidirectional"))
      (node (ref "X13") (pin "8") (pinfunction "8_8") (pintype "bidirectional"))
      (node (ref "X14") (pin "10") (pinfunction "10_10") (pintype "bidirectional"))
      (node (ref "X14") (pin "12") (pinfunction "12_12") (pintype "bidirectional"))
      (node (ref "X14") (pin "14") (pinfunction "14_14") (pintype "bidirectional"))
      (node (ref "X14") (pin "16") (pinfunction "16_16") (pintype "bidirectional"))
      (node (ref "X14") (pin "18") (pinfunction "18_18") (pintype "bidirectional"))
      (node (ref "X14") (pin "2") (pinfunction "2_2") (pintype "bidirectional"))
      (node (ref "X14") (pin "20") (pinfunction "20_20") (pintype "bidirectional"))
      (node (ref "X14") (pin "22") (pinfunction "22_22") (pintype "bidirectional"))
      (node (ref "X14") (pin "24") (pinfunction "24_24") (pintype "bidirectional"))
      (node (ref "X14") (pin "26") (pinfunction "26_26") (pintype "bidirectional"))
      (node (ref "X14") (pin "28") (pinfunction "28_28") (pintype "bidirectional"))
      (node (ref "X14") (pin "30") (pinfunction "30_30") (pintype "bidirectional"))
      (node (ref "X14") (pin "32") (pinfunction "32_32") (pintype "bidirectional"))
      (node (ref "X14") (pin "34") (pinfunction "34_34") (pintype "bidirectional"))
      (node (ref "X14") (pin "36") (pinfunction "36_36") (pintype "bidirectional"))
      (node (ref "X14") (pin "38") (pinfunction "38_38") (pintype "bidirectional"))
      (node (ref "X14") (pin "4") (pinfunction "4_4") (pintype "bidirectional"))
      (node (ref "X14") (pin "40") (pinfunction "40_40") (pintype "bidirectional"))
      (node (ref "X14") (pin "6") (pinfunction "6_6") (pintype "bidirectional"))
      (node (ref "X14") (pin "8") (pinfunction "8_8") (pintype "bidirectional"))
    )
    (net (code "90") (name "Net-(DD6C-IO_L3P_T0_DQS_PUDC_B_14)") (class "Default")
      (node (ref "DD6") (pin "B25") (pinfunction "IO_L3P_T0_DQS_PUDC_B_14_B25") (pintype "bidirectional"))
      (node (ref "R20") (pin "1") (pinfunction "1_1") (pintype "passive"))
    )
    (net (code "91") (name "Net-(VD1-C)") (class "Default")
      (node (ref "R142") (pin "2") (pinfunction "2_2") (pintype "passive"))
      (node (ref "VD1") (pin "1") (pinfunction "C_1") (pintype "passive"))
    )
    (net (code "92") (name "Net-(VD2-C)") (class "Default")
      (node (ref "R143") (pin "2") (pinfunction "2_2") (pintype "passive"))
      (node (ref "VD2") (pin "1") (pinfunction "C_1") (pintype "passive"))
    )
    (net (code "93") (name "Net-(VD3-C)") (class "Default")
      (node (ref "R144") (pin "2") (pinfunction "2_2") (pintype "passive"))
      (node (ref "VD3") (pin "1") (pinfunction "C_1") (pintype "passive"))
    )
    (net (code "94") (name "Net-(VD5-C)") (class "Default")
      (node (ref "R197") (pin "2") (pinfunction "2_2") (pintype "passive"))
      (node (ref "VD5") (pin "1") (pinfunction "C_1") (pintype "passive"))
    )
    (net (code "95") (name "Net-(VD7-C)") (class "Default")
      (node (ref "R145") (pin "2") (pinfunction "2_2") (pintype "passive"))
      (node (ref "VD7") (pin "1") (pinfunction "C_1") (pintype "passive"))
    )
    (net (code "96") (name "Net-(VD9-C)") (class "Default")
      (node (ref "R198") (pin "2") (pinfunction "2_2") (pintype "passive"))
      (node (ref "VD9") (pin "1") (pinfunction "C_1") (pintype "passive"))
    )
    (net (code "97") (name "Net-(VD15-C)") (class "Default")
      (node (ref "R199") (pin "2") (pinfunction "2_2") (pintype "passive"))
      (node (ref "VD15") (pin "1") (pinfunction "C_1") (pintype "passive"))
    )
    (net (code "98") (name "Net-(VD16-C)") (class "Default")
      (node (ref "R200") (pin "2") (pinfunction "2_2") (pintype "passive"))
      (node (ref "VD16") (pin "1") (pinfunction "C_1") (pintype "passive"))
    )
    (net (code "99") (name "P3V3") (class "Default")
      (node (ref "VD1") (pin "2") (pinfunction "A_2") (pintype "passive"))
      (node (ref "VD15") (pin "2") (pinfunction "A_2") (pintype "passive"))
      (node (ref "VD16") (pin "2") (pinfunction "A_2") (pintype "passive"))
      (node (ref "VD2") (pin "2") (pinfunction "A_2") (pintype "passive"))
      (node (ref "VD3") (pin "2") (pinfunction "A_2") (pintype "passive"))
      (node (ref "VD5") (pin "2") (pinfunction "A_2") (pintype "passive"))
      (node (ref "VD7") (pin "2") (pinfunction "A_2") (pintype "passive"))
      (node (ref "VD9") (pin "2") (pinfunction "A_2") (pintype "passive"))
    )
    (net (code "100") (name "unconnected-(DD6C-IO_L3N_T0_DQS_EMCCLK_14-PadB26)") (class "Default")
      (node (ref "DD6") (pin "B26") (pinfunction "IO_L3N_T0_DQS_EMCCLK_14_B26") (pintype "bidirectional+no_connect"))
    )
    (net (code "101") (name "unconnected-(DD6C-IO_L4N_T0_D05_14-PadA24)") (class "Default")
      (node (ref "DD6") (pin "A24") (pinfunction "IO_L4N_T0_D05_14_A24") (pintype "bidirectional+no_connect"))
    )
    (net (code "102") (name "unconnected-(DD6C-IO_L4P_T0_D04_14-PadA23)") (class "Default")
      (node (ref "DD6") (pin "A23") (pinfunction "IO_L4P_T0_D04_14_A23") (pintype "bidirectional+no_connect"))
    )
    (net (code "103") (name "unconnected-(DD6C-IO_L5N_T0_D07_14-PadC26)") (class "Default")
      (node (ref "DD6") (pin "C26") (pinfunction "IO_L5N_T0_D07_14_C26") (pintype "bidirectional+no_connect"))
    )
    (net (code "104") (name "unconnected-(DD6C-IO_L5P_T0_D06_14-PadD26)") (class "Default")
      (node (ref "DD6") (pin "D26") (pinfunction "IO_L5P_T0_D06_14_D26") (pintype "bidirectional+no_connect"))
    )
    (net (code "105") (name "unconnected-(DD6C-IO_L6N_T0_D08_VREF_14-PadC24)") (class "Default")
      (node (ref "DD6") (pin "C24") (pinfunction "IO_L6N_T0_D08_VREF_14_C24") (pintype "bidirectional+no_connect"))
    )
    (net (code "106") (name "unconnected-(DD6C-IO_L7N_T1_D10_14-PadC22)") (class "Default")
      (node (ref "DD6") (pin "C22") (pinfunction "IO_L7N_T1_D10_14_C22") (pintype "bidirectional+no_connect"))
    )
    (net (code "107") (name "unconnected-(DD6C-IO_L11N_T1_SRCC_14-PadD24)") (class "Default")
      (node (ref "DD6") (pin "D24") (pinfunction "IO_L11N_T1_SRCC_14_D24") (pintype "bidirectional+no_connect"))
    )
    (net (code "108") (name "unconnected-(DD6C-IO_L12N_T1_MRCC_14-PadE23)") (class "Default")
      (node (ref "DD6") (pin "E23") (pinfunction "IO_L12N_T1_MRCC_14_E23") (pintype "bidirectional+no_connect"))
    )
    (net (code "109") (name "unconnected-(DD6C-IO_L15N_T2_DQS_DOUT_CSO_B_14-PadD25)") (class "Default")
      (node (ref "DD6") (pin "D25") (pinfunction "IO_L15N_T2_DQS_DOUT_CSO_B_14_D25") (pintype "bidirectional+no_connect"))
    )
    (net (code "110") (name "unconnected-(DD6C-IO_L15P_T2_DQS_RDWR_B_14-PadE25)") (class "Default")
      (node (ref "DD6") (pin "E25") (pinfunction "IO_L15P_T2_DQS_RDWR_B_14_E25") (pintype "bidirectional+no_connect"))
    )
    (net (code "111") (name "unconnected-(DD6C-IO_L17N_T2_A13_D29_14-PadE26)") (class "Default")
      (node (ref "DD6") (pin "E26") (pinfunction "IO_L17N_T2_A13_D29_14_E26") (pintype "bidirectional+no_connect"))
    )
    (net (code "112") (name "unconnected-(X11-Pad1)") (class "Default")
      (node (ref "X11") (pin "1") (pinfunction "1_1") (pintype "bidirectional+no_connect"))
    )
    (net (code "113") (name "unconnected-(X11-Pad5)") (class "Default")
      (node (ref "X11") (pin "5") (pinfunction "5_5") (pintype "bidirectional+no_connect"))
    )
    (net (code "114") (name "unconnected-(X11-Pad39)") (class "Default")
      (node (ref "X11") (pin "39") (pinfunction "39_39") (pintype "bidirectional+no_connect"))
    )
    (net (code "115") (name "unconnected-(X12-Pad1)") (class "Default")
      (node (ref "X12") (pin "1") (pinfunction "1_1") (pintype "bidirectional+no_connect"))
    )
    (net (code "116") (name "unconnected-(X12-Pad5)") (class "Default")
      (node (ref "X12") (pin "5") (pinfunction "5_5") (pintype "bidirectional+no_connect"))
    )
    (net (code "117") (name "unconnected-(X12-Pad39)") (class "Default")
      (node (ref "X12") (pin "39") (pinfunction "39_39") (pintype "bidirectional+no_connect"))
    )
    (net (code "118") (name "unconnected-(X13-Pad1)") (class "Default")
      (node (ref "X13") (pin "1") (pinfunction "1_1") (pintype "bidirectional+no_connect"))
    )
    (net (code "119") (name "unconnected-(X13-Pad5)") (class "Default")
      (node (ref "X13") (pin "5") (pinfunction "5_5") (pintype "bidirectional+no_connect"))
    )
    (net (code "120") (name "unconnected-(X13-Pad39)") (class "Default")
      (node (ref "X13") (pin "39") (pinfunction "39_39") (pintype "bidirectional+no_connect"))
    )
    (net (code "121") (name "unconnected-(X14-Pad1)") (class "Default")
      (node (ref "X14") (pin "1") (pinfunction "1_1") (pintype "bidirectional+no_connect"))
    )
    (net (code "122") (name "unconnected-(X14-Pad5)") (class "Default")
      (node (ref "X14") (pin "5") (pinfunction "5_5") (pintype "bidirectional+no_connect"))
    )
    (net (code "123") (name "unconnected-(X14-Pad39)") (class "Default")
      (node (ref "X14") (pin "39") (pinfunction "39_39") (pintype "bidirectional+no_connect"))
    )
  )
)
